# Digital.net
KiCad netlist of a schematic drawn in Altium Designer
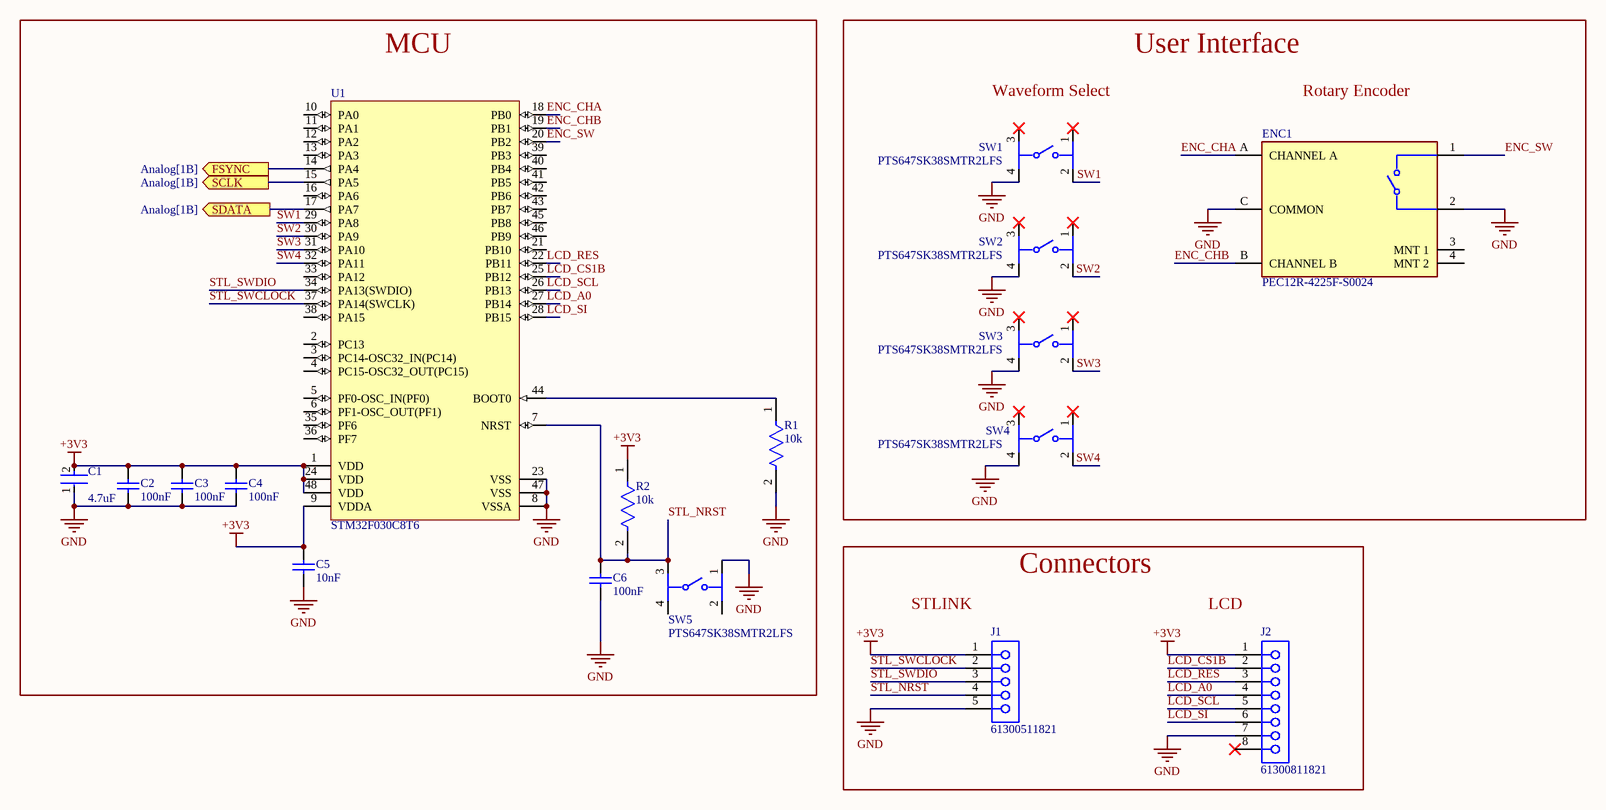
[diagram p0: Digital.SchDoc]

(export (version "E")
  (design (tool "Eeschema 10.0.6"))
  (components
    (comp (ref "C1")
      (value "4.7uF")
      (footprint "FP-GRM219-0_15-0_1-IPC_B")
      (description "Chip Multilayer Ceramic Capacitors for General Purpose, 0805, 4.7uF, X5R, 15%, 20%, 25V")
      (libsource (lib "Altium Content Vault") (part "236180d848d6139a670b325ea6854c9"))
    )
    (comp (ref "C2")
      (value "100nF")
      (footprint "CAPC1608X87X45LL20T05")
      (description "Ceramic 100nF X7R 16V 5%")
      (fields (field (name "PART NUMBER") "C0603X104J4RACTU") (field (name "MANUFACTURER") "Kemet"))
      (libsource (lib "Altium Content Vault") (part "CAP"))
    )
    (comp (ref "C3")
      (value "100nF")
      (footprint "CAPC1608X87X45LL20T05")
      (description "Ceramic 100nF X7R 16V 5%")
      (fields (field (name "PART NUMBER") "C0603X104J4RACTU") (field (name "MANUFACTURER") "Kemet"))
      (libsource (lib "Altium Content Vault") (part "CAP"))
    )
    (comp (ref "C4")
      (value "100nF")
      (footprint "CAPC1608X87X45LL20T05")
      (description "Ceramic 100nF X7R 16V 5%")
      (fields (field (name "PART NUMBER") "C0603X104J4RACTU") (field (name "MANUFACTURER") "Kemet"))
      (libsource (lib "Altium Content Vault") (part "CAP"))
    )
    (comp (ref "C5")
      (value "10nF")
      (footprint "CAPC1206(3216)150_L")
      (description "CAP 10nF 10V ±5% 1206 (3216 Metric) Thickness 1.45mm SMD")
      (fields (field (name "TOLERANCE") "Â±5%"))
      (libsource (lib "Altium Content Vault") (part "CAP"))
    )
    (comp (ref "C6")
      (value "100nF")
      (footprint "CAPC1608X87X45LL20T05")
      (description "Ceramic 100nF X7R 16V 5%")
      (fields (field (name "PART NUMBER") "C0603X104J4RACTU") (field (name "MANUFACTURER") "Kemet"))
      (libsource (lib "Altium Content Vault") (part "CAP"))
    )
    (comp (ref "ENC1")
      (value "PEC12R-4225F-S0024")
      (footprint "FP-PEC12R-4225F-S0024-MFG")
      (description "ROTARY ENCODER MECHANICAL 24PPR")
      (libsource (lib "Altium Content Vault") (part "084942c7348c54a7e5fe2df5ed54478"))
    )
    (comp (ref "J1")
      (value "61300511821")
      (footprint "61300511821")
      (libsource (lib "Altium Content Vault") (part "Header_Female_1R_05P"))
    )
    (comp (ref "J2")
      (value "61300811821")
      (footprint "61300811821")
      (libsource (lib "Altium Content Vault") (part "Header_Female_1R_08P"))
    )
    (comp (ref "R1")
      (value "10k")
      (footprint "FP-TFCR0402-IPC_B")
      (description "RES Thin Film,  10kΩ, 0.1%, 0.063W, 50ppm/°C, 0402")
      (libsource (lib "Altium Content Vault") (part "1029c3af85768c4190bb7ad29bc67b5"))
    )
    (comp (ref "R2")
      (value "10k")
      (footprint "FP-TFCR0402-IPC_B")
      (description "RES Thin Film,  10kΩ, 0.1%, 0.063W, 50ppm/°C, 0402")
      (libsource (lib "Altium Content Vault") (part "1029c3af85768c4190bb7ad29bc67b5"))
    )
    (comp (ref "SW1")
      (value "PTS647SK38SMTR2LFS")
      (footprint "FP-PTS647SK38SMTR2LFS-MFG")
      (description "TACT 4.5 X 4.5, 3.8 MM H, 2.5N,")
      (libsource (lib "Altium Content Vault") (part "1adf0dd01260c80cf25a44bfd6b99ba"))
    )
    (comp (ref "SW2")
      (value "PTS647SK38SMTR2LFS")
      (footprint "FP-PTS647SK38SMTR2LFS-MFG")
      (description "TACT 4.5 X 4.5, 3.8 MM H, 2.5N,")
      (libsource (lib "Altium Content Vault") (part "1adf0dd01260c80cf25a44bfd6b99ba"))
    )
    (comp (ref "SW3")
      (value "PTS647SK38SMTR2LFS")
      (footprint "FP-PTS647SK38SMTR2LFS-MFG")
      (description "TACT 4.5 X 4.5, 3.8 MM H, 2.5N,")
      (libsource (lib "Altium Content Vault") (part "1adf0dd01260c80cf25a44bfd6b99ba"))
    )
    (comp (ref "SW4")
      (value "PTS647SK38SMTR2LFS")
      (footprint "FP-PTS647SK38SMTR2LFS-MFG")
      (description "TACT 4.5 X 4.5, 3.8 MM H, 2.5N,")
      (libsource (lib "Altium Content Vault") (part "1adf0dd01260c80cf25a44bfd6b99ba"))
    )
    (comp (ref "SW5")
      (value "PTS647SK38SMTR2LFS")
      (footprint "FP-PTS647SK38SMTR2LFS-MFG")
      (description "TACT 4.5 X 4.5, 3.8 MM H, 2.5N,")
      (libsource (lib "Altium Content Vault") (part "1adf0dd01260c80cf25a44bfd6b99ba"))
    )
    (comp (ref "U1")
      (value "STM32F030C8T6")
      (footprint "STM-LQFP48_M")
      (fields
        (field (name "MANUFACTURER") "STMicroelectronics")
        (field (name "PARTNUMBER") "STM32F030C8T6TR")
      )
      (libsource (lib "Altium Content Vault") (part "MC-ARM-STM32F030-LQFP48_A"))
    )
  )
  (nets
    (net (code "1") (name "+3V3") (class "Default")
      (node (ref "C1") (pin "2") (pinfunction "2_2") (pintype "passive"))
      (node (ref "C2") (pin "2") (pinfunction "2_2") (pintype "passive"))
      (node (ref "C3") (pin "2") (pinfunction "2_2") (pintype "passive"))
      (node (ref "C4") (pin "2") (pinfunction "2_2") (pintype "passive"))
      (node (ref "C5") (pin "2") (pinfunction "2_2") (pintype "passive"))
      (node (ref "J1") (pin "1") (pinfunction "1_1") (pintype "passive"))
      (node (ref "J2") (pin "1") (pinfunction "1_1") (pintype "passive"))
      (node (ref "R2") (pin "1") (pinfunction "1_1") (pintype "passive"))
      (node (ref "U1") (pin "1") (pinfunction "VDD_1") (pintype "power_in"))
      (node (ref "U1") (pin "24") (pinfunction "VDD_24") (pintype "power_in"))
      (node (ref "U1") (pin "48") (pinfunction "VDD_48") (pintype "power_in"))
      (node (ref "U1") (pin "9") (pinfunction "VDDA_9") (pintype "power_in"))
    )
    (net (code "2") (name "/ENC_CHA") (class "Default")
      (node (ref "ENC1") (pin "A") (pinfunction "CHANNEL_A_A") (pintype "passive"))
      (node (ref "U1") (pin "18") (pinfunction "PB0_18") (pintype "bidirectional"))
    )
    (net (code "3") (name "/ENC_CHB") (class "Default")
      (node (ref "ENC1") (pin "B") (pinfunction "CHANNEL_B_B") (pintype "passive"))
      (node (ref "U1") (pin "19") (pinfunction "PB1_19") (pintype "bidirectional"))
    )
    (net (code "4") (name "/ENC_SW") (class "Default")
      (node (ref "ENC1") (pin "1") (pinfunction "1_1") (pintype "passive"))
      (node (ref "U1") (pin "20") (pinfunction "PB2_20") (pintype "bidirectional"))
    )
    (net (code "5") (name "/FSYNC") (class "Default")
      (node (ref "U1") (pin "14") (pinfunction "PA4_14") (pintype "output"))
    )
    (net (code "6") (name "/LCD_A0") (class "Default")
      (node (ref "J2") (pin "4") (pinfunction "4_4") (pintype "passive"))
      (node (ref "U1") (pin "27") (pinfunction "PB14_27") (pintype "bidirectional"))
    )
    (net (code "7") (name "/LCD_CS1B") (class "Default")
      (node (ref "J2") (pin "2") (pinfunction "2_2") (pintype "passive"))
      (node (ref "U1") (pin "25") (pinfunction "PB12_25") (pintype "bidirectional"))
    )
    (net (code "8") (name "/LCD_RES") (class "Default")
      (node (ref "J2") (pin "3") (pinfunction "3_3") (pintype "passive"))
      (node (ref "U1") (pin "22") (pinfunction "PB11_22") (pintype "bidirectional"))
    )
    (net (code "9") (name "/LCD_SCL") (class "Default")
      (node (ref "J2") (pin "5") (pinfunction "5_5") (pintype "passive"))
      (node (ref "U1") (pin "26") (pinfunction "PB13_26") (pintype "bidirectional"))
    )
    (net (code "10") (name "/LCD_SI") (class "Default")
      (node (ref "J2") (pin "6") (pinfunction "6_6") (pintype "passive"))
      (node (ref "U1") (pin "28") (pinfunction "PB15_28") (pintype "bidirectional"))
    )
    (net (code "11") (name "/SCLK") (class "Default")
      (node (ref "U1") (pin "15") (pinfunction "PA5_15") (pintype "output"))
    )
    (net (code "12") (name "/SDATA") (class "Default")
      (node (ref "U1") (pin "17") (pinfunction "PA7_17") (pintype "output"))
    )
    (net (code "13") (name "/STL_NRST") (class "Default")
      (node (ref "C6") (pin "2") (pinfunction "2_2") (pintype "passive"))
      (node (ref "J1") (pin "4") (pinfunction "4_4") (pintype "passive"))
      (node (ref "R2") (pin "2") (pinfunction "2_2") (pintype "passive"))
      (node (ref "SW5") (pin "3") (pinfunction "3_3") (pintype "passive"))
      (node (ref "U1") (pin "7") (pinfunction "NRST_7") (pintype "bidirectional"))
    )
    (net (code "14") (name "/STL_SWCLOCK") (class "Default")
      (node (ref "J1") (pin "2") (pinfunction "2_2") (pintype "passive"))
      (node (ref "U1") (pin "37") (pinfunction "PA14(SWCLK)_37") (pintype "bidirectional"))
    )
    (net (code "15") (name "/STL_SWDIO") (class "Default")
      (node (ref "J1") (pin "3") (pinfunction "3_3") (pintype "passive"))
      (node (ref "U1") (pin "34") (pinfunction "PA13(SWDIO)_34") (pintype "bidirectional"))
    )
    (net (code "16") (name "/SW1") (class "Default")
      (node (ref "SW1") (pin "2") (pinfunction "2_2") (pintype "passive"))
      (node (ref "U1") (pin "29") (pinfunction "PA8_29") (pintype "bidirectional"))
    )
    (net (code "17") (name "/SW2") (class "Default")
      (node (ref "SW2") (pin "2") (pinfunction "2_2") (pintype "passive"))
      (node (ref "U1") (pin "30") (pinfunction "PA9_30") (pintype "bidirectional"))
    )
    (net (code "18") (name "/SW3") (class "Default")
      (node (ref "SW3") (pin "2") (pinfunction "2_2") (pintype "passive"))
      (node (ref "U1") (pin "31") (pinfunction "PA10_31") (pintype "bidirectional"))
    )
    (net (code "19") (name "/SW4") (class "Default")
      (node (ref "SW4") (pin "2") (pinfunction "2_2") (pintype "passive"))
      (node (ref "U1") (pin "32") (pinfunction "PA11_32") (pintype "bidirectional"))
    )
    (net (code "20") (name "GND") (class "Default")
      (node (ref "C1") (pin "1") (pinfunction "1_1") (pintype "passive"))
      (node (ref "C2") (pin "1") (pinfunction "1_1") (pintype "passive"))
      (node (ref "C3") (pin "1") (pinfunction "1_1") (pintype "passive"))
      (node (ref "C4") (pin "1") (pinfunction "1_1") (pintype "passive"))
      (node (ref "C5") (pin "1") (pinfunction "1_1") (pintype "passive"))
      (node (ref "C6") (pin "1") (pinfunction "1_1") (pintype "passive"))
      (node (ref "ENC1") (pin "2") (pinfunction "2_2") (pintype "passive"))
      (node (ref "ENC1") (pin "C") (pinfunction "COMMON_C") (pintype "passive"))
      (node (ref "J1") (pin "5") (pinfunction "5_5") (pintype "passive"))
      (node (ref "J2") (pin "7") (pinfunction "7_7") (pintype "passive"))
      (node (ref "R1") (pin "2") (pinfunction "2_2") (pintype "passive"))
      (node (ref "SW1") (pin "4") (pinfunction "4_4") (pintype "passive"))
      (node (ref "SW2") (pin "4") (pinfunction "4_4") (pintype "passive"))
      (node (ref "SW3") (pin "4") (pinfunction "4_4") (pintype "passive"))
      (node (ref "SW4") (pin "4") (pinfunction "4_4") (pintype "passive"))
      (node (ref "SW5") (pin "1") (pinfunction "1_1") (pintype "passive"))
      (node (ref "U1") (pin "23") (pinfunction "VSS_23") (pintype "power_in"))
      (node (ref "U1") (pin "47") (pinfunction "VSS_47") (pintype "power_in"))
      (node (ref "U1") (pin "8") (pinfunction "VSSA_8") (pintype "power_in"))
    )
    (net (code "21") (name "Net-(U1-BOOT0)") (class "Default")
      (node (ref "R1") (pin "1") (pinfunction "1_1") (pintype "passive"))
      (node (ref "U1") (pin "44") (pinfunction "BOOT0_44") (pintype "input"))
    )
    (net (code "22") (name "unconnected-(ENC1-MNT_1-Pad3)") (class "Default")
      (node (ref "ENC1") (pin "3") (pinfunction "MNT_1_3") (pintype "passive"))
    )
    (net (code "23") (name "unconnected-(ENC1-MNT_2-Pad4)") (class "Default")
      (node (ref "ENC1") (pin "4") (pinfunction "MNT_2_4") (pintype "passive"))
    )
    (net (code "24") (name "unconnected-(J2-Pad8)") (class "Default")
      (node (ref "J2") (pin "8") (pinfunction "8_8") (pintype "passive+no_connect"))
    )
    (net (code "25") (name "unconnected-(SW1-Pad1)") (class "Default")
      (node (ref "SW1") (pin "1") (pinfunction "1_1") (pintype "passive+no_connect"))
    )
    (net (code "26") (name "unconnected-(SW1-Pad3)") (class "Default")
      (node (ref "SW1") (pin "3") (pinfunction "3_3") (pintype "passive+no_connect"))
    )
    (net (code "27") (name "unconnected-(SW2-Pad1)") (class "Default")
      (node (ref "SW2") (pin "1") (pinfunction "1_1") (pintype "passive+no_connect"))
    )
    (net (code "28") (name "unconnected-(SW2-Pad3)") (class "Default")
      (node (ref "SW2") (pin "3") (pinfunction "3_3") (pintype "passive+no_connect"))
    )
    (net (code "29") (name "unconnected-(SW3-Pad1)") (class "Default")
      (node (ref "SW3") (pin "1") (pinfunction "1_1") (pintype "passive+no_connect"))
    )
    (net (code "30") (name "unconnected-(SW3-Pad3)") (class "Default")
      (node (ref "SW3") (pin "3") (pinfunction "3_3") (pintype "passive+no_connect"))
    )
    (net (code "31") (name "unconnected-(SW4-Pad1)") (class "Default")
      (node (ref "SW4") (pin "1") (pinfunction "1_1") (pintype "passive+no_connect"))
    )
    (net (code "32") (name "unconnected-(SW4-Pad3)") (class "Default")
      (node (ref "SW4") (pin "3") (pinfunction "3_3") (pintype "passive+no_connect"))
    )
    (net (code "33") (name "unconnected-(SW5-Pad2)") (class "Default")
      (node (ref "SW5") (pin "2") (pinfunction "2_2") (pintype "passive"))
    )
    (net (code "34") (name "unconnected-(SW5-Pad4)") (class "Default")
      (node (ref "SW5") (pin "4") (pinfunction "4_4") (pintype "passive"))
    )
    (net (code "35") (name "unconnected-(U1-PA0-Pad10)") (class "Default")
      (node (ref "U1") (pin "10") (pinfunction "PA0_10") (pintype "bidirectional"))
    )
    (net (code "36") (name "unconnected-(U1-PA1-Pad11)") (class "Default")
      (node (ref "U1") (pin "11") (pinfunction "PA1_11") (pintype "bidirectional"))
    )
    (net (code "37") (name "unconnected-(U1-PA2-Pad12)") (class "Default")
      (node (ref "U1") (pin "12") (pinfunction "PA2_12") (pintype "bidirectional"))
    )
    (net (code "38") (name "unconnected-(U1-PA3-Pad13)") (class "Default")
      (node (ref "U1") (pin "13") (pinfunction "PA3_13") (pintype "bidirectional"))
    )
    (net (code "39") (name "unconnected-(U1-PA6-Pad16)") (class "Default")
      (node (ref "U1") (pin "16") (pinfunction "PA6_16") (pintype "bidirectional"))
    )
    (net (code "40") (name "unconnected-(U1-PA12-Pad33)") (class "Default")
      (node (ref "U1") (pin "33") (pinfunction "PA12_33") (pintype "bidirectional"))
    )
    (net (code "41") (name "unconnected-(U1-PA15-Pad38)") (class "Default")
      (node (ref "U1") (pin "38") (pinfunction "PA15_38") (pintype "bidirectional"))
    )
    (net (code "42") (name "unconnected-(U1-PB3-Pad39)") (class "Default")
      (node (ref "U1") (pin "39") (pinfunction "PB3_39") (pintype "bidirectional"))
    )
    (net (code "43") (name "unconnected-(U1-PB4-Pad40)") (class "Default")
      (node (ref "U1") (pin "40") (pinfunction "PB4_40") (pintype "bidirectional"))
    )
    (net (code "44") (name "unconnected-(U1-PB5-Pad41)") (class "Default")
      (node (ref "U1") (pin "41") (pinfunction "PB5_41") (pintype "bidirectional"))
    )
    (net (code "45") (name "unconnected-(U1-PB6-Pad42)") (class "Default")
      (node (ref "U1") (pin "42") (pinfunction "PB6_42") (pintype "bidirectional"))
    )
    (net (code "46") (name "unconnected-(U1-PB7-Pad43)") (class "Default")
      (node (ref "U1") (pin "43") (pinfunction "PB7_43") (pintype "bidirectional"))
    )
    (net (code "47") (name "unconnected-(U1-PB8-Pad45)") (class "Default")
      (node (ref "U1") (pin "45") (pinfunction "PB8_45") (pintype "bidirectional"))
    )
    (net (code "48") (name "unconnected-(U1-PB9-Pad46)") (class "Default")
      (node (ref "U1") (pin "46") (pinfunction "PB9_46") (pintype "bidirectional"))
    )
    (net (code "49") (name "unconnected-(U1-PB10-Pad21)") (class "Default")
      (node (ref "U1") (pin "21") (pinfunction "PB10_21") (pintype "bidirectional"))
    )
    (net (code "50") (name "unconnected-(U1-PC13-Pad2)") (class "Default")
      (node (ref "U1") (pin "2") (pinfunction "PC13_2") (pintype "bidirectional"))
    )
    (net (code "51") (name "unconnected-(U1-PC14-OSC32_IN(PC14)-Pad3)") (class "Default")
      (node (ref "U1") (pin "3") (pinfunction "PC14-OSC32_IN(PC14)_3") (pintype "bidirectional"))
    )
    (net (code "52") (name "unconnected-(U1-PC15-OSC32_OUT(PC15)-Pad4)") (class "Default")
      (node (ref "U1") (pin "4") (pinfunction "PC15-OSC32_OUT(PC15)_4") (pintype "bidirectional"))
    )
    (net (code "53") (name "unconnected-(U1-PF0-OSC_IN(PF0)-Pad5)") (class "Default")
      (node (ref "U1") (pin "5") (pinfunction "PF0-OSC_IN(PF0)_5") (pintype "bidirectional"))
    )
    (net (code "54") (name "unconnected-(U1-PF1-OSC_OUT(PF1)-Pad6)") (class "Default")
      (node (ref "U1") (pin "6") (pinfunction "PF1-OSC_OUT(PF1)_6") (pintype "bidirectional"))
    )
    (net (code "55") (name "unconnected-(U1-PF6-Pad35)") (class "Default")
      (node (ref "U1") (pin "35") (pinfunction "PF6_35") (pintype "bidirectional"))
    )
    (net (code "56") (name "unconnected-(U1-PF7-Pad36)") (class "Default")
      (node (ref "U1") (pin "36") (pinfunction "PF7_36") (pintype "bidirectional"))
    )
  )
)
